# STEM.net
KiCad netlist of a schematic drawn in EAGLE
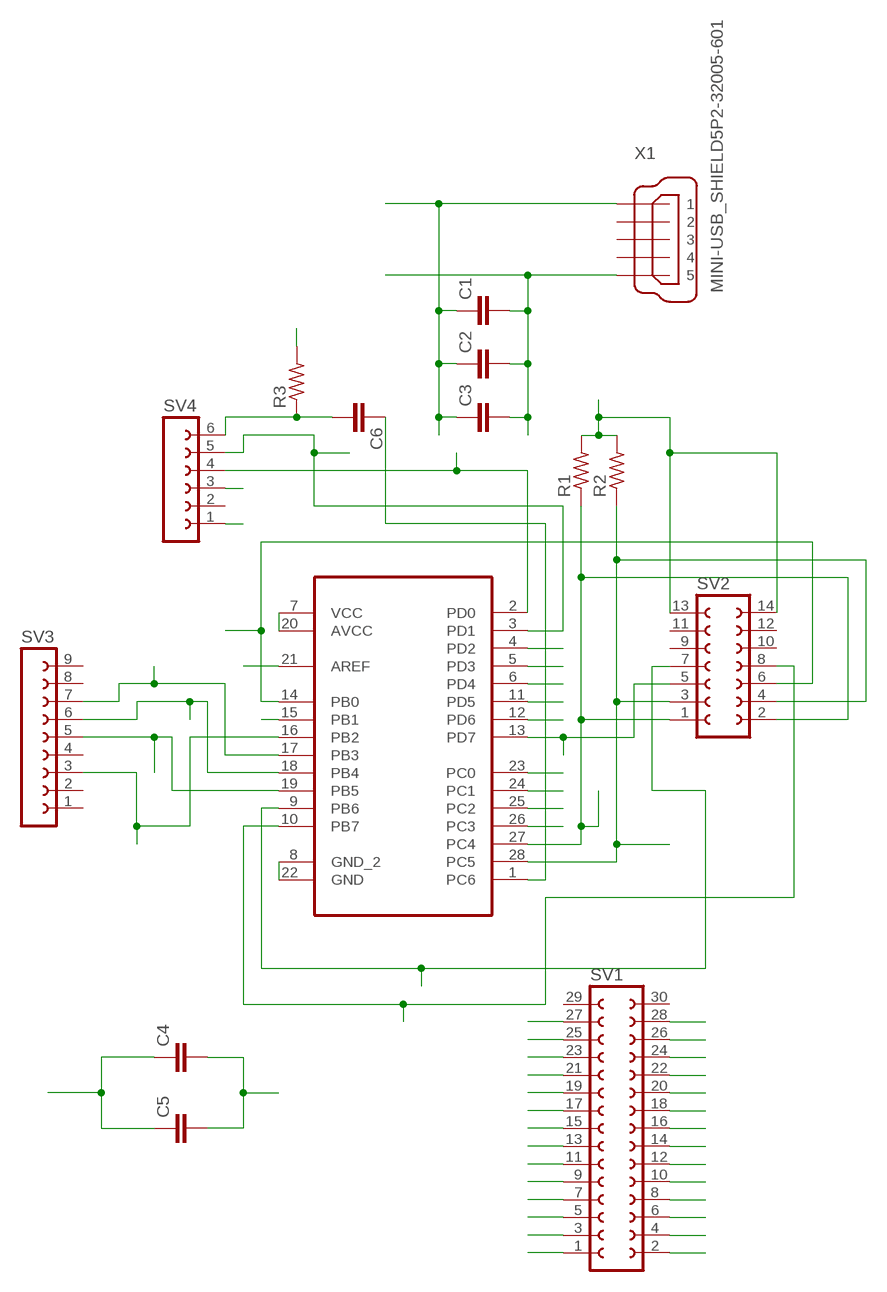
[diagram p0: schematic, sheet 1]

(export (version "E")
  (design (tool "Eeschema 10.0.6"))
  (components
    (comp (ref "C1")
      (value "C2,5-3")
      (footprint "eagle-import:C2.5-3")
      (libsource (lib "eagle-import") (part "C2,5-3"))
    )
    (comp (ref "C2")
      (value "C2,5-3")
      (footprint "eagle-import:C2.5-3")
      (libsource (lib "eagle-import") (part "C2,5-3"))
    )
    (comp (ref "C3")
      (value "C2,5-3")
      (footprint "eagle-import:C2.5-3")
      (libsource (lib "eagle-import") (part "C2,5-3"))
    )
    (comp (ref "C4")
      (value "C2,5-3")
      (footprint "eagle-import:C2.5-3")
      (libsource (lib "eagle-import") (part "C2,5-3"))
    )
    (comp (ref "C5")
      (value "C2,5-3")
      (footprint "eagle-import:C2.5-3")
      (libsource (lib "eagle-import") (part "C2,5-3"))
    )
    (comp (ref "C6")
      (value "C2,5-3")
      (footprint "eagle-import:C2.5-3")
      (libsource (lib "eagle-import") (part "C2,5-3"))
    )
    (comp (ref "R1")
      (value "R-US_0204/7")
      (footprint "eagle-import:0204_7")
      (libsource (lib "eagle-import") (part "R-US_0204/7"))
    )
    (comp (ref "R2")
      (value "R-US_0204/7")
      (footprint "eagle-import:0204_7")
      (libsource (lib "eagle-import") (part "R-US_0204/7"))
    )
    (comp (ref "R3")
      (value "R-US_0204/7")
      (footprint "eagle-import:0204_7")
      (libsource (lib "eagle-import") (part "R-US_0204/7"))
    )
    (comp (ref "SV1")
      (value "FE15-2")
      (footprint "eagle-import:FE15-2")
      (libsource (lib "eagle-import") (part "FE15-2"))
    )
    (comp (ref "SV2")
      (value "FE07-2")
      (footprint "eagle-import:FE07-2")
      (libsource (lib "eagle-import") (part "FE07-2"))
    )
    (comp (ref "SV3")
      (value "FE09-1")
      (footprint "eagle-import:FE09")
      (libsource (lib "eagle-import") (part "FE09-1"))
    )
    (comp (ref "SV4")
      (value "FE06-1")
      (footprint "eagle-import:FE06")
      (libsource (lib "eagle-import") (part "FE06-1"))
    )
    (comp (ref "U1")
      (value "ATMEGA328P-PU")
      (footprint "eagle-import:DIP254P762X457-28")
      (libsource (lib "eagle-import") (part "ATMEGA328P-PU"))
    )
    (comp (ref "X1")
      (value "MINI-USB_SHIELD5P2-32005-601")
      (footprint "eagle-import:32005-601")
      (libsource (lib "eagle-import") (part "MINI-USB_SHIELD5P2-32005-601"))
    )
  )
  (nets
    (net (code "1") (name "/AREF") (class "Default")
      (node (ref "C4") (pin "1") (pinfunction "1_1") (pintype "passive"))
      (node (ref "C5") (pin "1") (pinfunction "1_1") (pintype "passive"))
      (node (ref "SV1") (pin "14") (pinfunction "14_14") (pintype "passive"))
      (node (ref "U1") (pin "21") (pinfunction "AREF_21") (pintype "input"))
    )
    (net (code "2") (name "/GND") (class "Default")
      (node (ref "C1") (pin "2") (pinfunction "2_2") (pintype "passive"))
      (node (ref "C2") (pin "2") (pinfunction "2_2") (pintype "passive"))
      (node (ref "C3") (pin "2") (pinfunction "2_2") (pintype "passive"))
      (node (ref "C4") (pin "2") (pinfunction "2_2") (pintype "passive"))
      (node (ref "C5") (pin "2") (pinfunction "2_2") (pintype "passive"))
      (node (ref "SV1") (pin "13") (pinfunction "13_13") (pintype "passive"))
      (node (ref "SV1") (pin "16") (pinfunction "16_16") (pintype "passive"))
      (node (ref "SV4") (pin "1") (pinfunction "1_1") (pintype "passive"))
      (node (ref "U1") (pin "22") (pinfunction "GND_22") (pintype "passive"))
      (node (ref "U1") (pin "8") (pinfunction "GND_2_8") (pintype "passive"))
      (node (ref "X1") (pin "5") (pinfunction "5_5") (pintype "passive"))
    )
    (net (code "3") (name "/PB0") (class "Default")
      (node (ref "SV1") (pin "1") (pinfunction "1_1") (pintype "passive"))
      (node (ref "SV2") (pin "6") (pinfunction "6_6") (pintype "passive"))
      (node (ref "U1") (pin "14") (pinfunction "PB0_14") (pintype "bidirectional"))
    )
    (net (code "4") (name "/PB1") (class "Default")
      (node (ref "SV1") (pin "2") (pinfunction "2_2") (pintype "passive"))
      (node (ref "U1") (pin "15") (pinfunction "PB1_15") (pintype "bidirectional"))
    )
    (net (code "5") (name "/PB2") (class "Default")
      (node (ref "SV1") (pin "4") (pinfunction "4_4") (pintype "passive"))
      (node (ref "SV3") (pin "3") (pinfunction "3_3") (pintype "passive"))
      (node (ref "U1") (pin "16") (pinfunction "PB2_16") (pintype "bidirectional"))
    )
    (net (code "6") (name "/PB3") (class "Default")
      (node (ref "SV1") (pin "6") (pinfunction "6_6") (pintype "passive"))
      (node (ref "SV3") (pin "7") (pinfunction "7_7") (pintype "passive"))
      (node (ref "U1") (pin "17") (pinfunction "PB3_17") (pintype "bidirectional"))
    )
    (net (code "7") (name "/PB4") (class "Default")
      (node (ref "SV1") (pin "8") (pinfunction "8_8") (pintype "passive"))
      (node (ref "SV3") (pin "6") (pinfunction "6_6") (pintype "passive"))
      (node (ref "U1") (pin "18") (pinfunction "PB4_18") (pintype "bidirectional"))
    )
    (net (code "8") (name "/PB5") (class "Default")
      (node (ref "SV1") (pin "10") (pinfunction "10_10") (pintype "passive"))
      (node (ref "SV3") (pin "5") (pinfunction "5_5") (pintype "passive"))
      (node (ref "U1") (pin "19") (pinfunction "PB5_19") (pintype "bidirectional"))
    )
    (net (code "9") (name "/PB6") (class "Default")
      (node (ref "SV1") (pin "11") (pinfunction "11_11") (pintype "passive"))
      (node (ref "SV2") (pin "7") (pinfunction "7_7") (pintype "passive"))
      (node (ref "U1") (pin "9") (pinfunction "PB6_9") (pintype "bidirectional"))
    )
    (net (code "10") (name "/PB7") (class "Default")
      (node (ref "SV1") (pin "9") (pinfunction "9_9") (pintype "passive"))
      (node (ref "SV2") (pin "8") (pinfunction "8_8") (pintype "passive"))
      (node (ref "U1") (pin "10") (pinfunction "PB7_10") (pintype "bidirectional"))
    )
    (net (code "11") (name "/PC0") (class "Default")
      (node (ref "SV1") (pin "18") (pinfunction "18_18") (pintype "passive"))
      (node (ref "U1") (pin "23") (pinfunction "PC0_23") (pintype "bidirectional"))
    )
    (net (code "12") (name "/PC1") (class "Default")
      (node (ref "SV1") (pin "20") (pinfunction "20_20") (pintype "passive"))
      (node (ref "U1") (pin "24") (pinfunction "PC1_24") (pintype "bidirectional"))
    )
    (net (code "13") (name "/PC2") (class "Default")
      (node (ref "SV1") (pin "22") (pinfunction "22_22") (pintype "passive"))
      (node (ref "U1") (pin "25") (pinfunction "PC2_25") (pintype "bidirectional"))
    )
    (net (code "14") (name "/PC3") (class "Default")
      (node (ref "SV1") (pin "24") (pinfunction "24_24") (pintype "passive"))
      (node (ref "U1") (pin "26") (pinfunction "PC3_26") (pintype "bidirectional"))
    )
    (net (code "15") (name "/PC4") (class "Default")
      (node (ref "R1") (pin "1") (pinfunction "1_1") (pintype "passive"))
      (node (ref "SV1") (pin "26") (pinfunction "26_26") (pintype "passive"))
      (node (ref "SV2") (pin "1") (pinfunction "1_1") (pintype "passive"))
      (node (ref "SV2") (pin "2") (pinfunction "2_2") (pintype "passive"))
      (node (ref "U1") (pin "27") (pinfunction "PC4_27") (pintype "bidirectional"))
    )
    (net (code "16") (name "/PC5") (class "Default")
      (node (ref "R2") (pin "1") (pinfunction "1_1") (pintype "passive"))
      (node (ref "SV1") (pin "28") (pinfunction "28_28") (pintype "passive"))
      (node (ref "SV2") (pin "3") (pinfunction "3_3") (pintype "passive"))
      (node (ref "SV2") (pin "4") (pinfunction "4_4") (pintype "passive"))
      (node (ref "U1") (pin "28") (pinfunction "PC5_28") (pintype "bidirectional"))
    )
    (net (code "17") (name "/PC6") (class "Default")
      (node (ref "C6") (pin "1") (pinfunction "1_1") (pintype "passive"))
      (node (ref "SV1") (pin "27") (pinfunction "27_27") (pintype "passive"))
      (node (ref "U1") (pin "1") (pinfunction "PC6_1") (pintype "bidirectional"))
    )
    (net (code "18") (name "/PD0") (class "Default")
      (node (ref "SV1") (pin "25") (pinfunction "25_25") (pintype "passive"))
      (node (ref "SV4") (pin "4") (pinfunction "4_4") (pintype "passive"))
      (node (ref "U1") (pin "2") (pinfunction "PD0_2") (pintype "bidirectional"))
    )
    (net (code "19") (name "/PD1") (class "Default")
      (node (ref "SV1") (pin "23") (pinfunction "23_23") (pintype "passive"))
      (node (ref "SV4") (pin "5") (pinfunction "5_5") (pintype "passive"))
      (node (ref "U1") (pin "3") (pinfunction "PD1_3") (pintype "bidirectional"))
    )
    (net (code "20") (name "/PD2") (class "Default")
      (node (ref "SV1") (pin "21") (pinfunction "21_21") (pintype "passive"))
      (node (ref "U1") (pin "4") (pinfunction "PD2_4") (pintype "bidirectional"))
    )
    (net (code "21") (name "/PD3") (class "Default")
      (node (ref "SV1") (pin "19") (pinfunction "19_19") (pintype "passive"))
      (node (ref "U1") (pin "5") (pinfunction "PD3_5") (pintype "bidirectional"))
    )
    (net (code "22") (name "/PD4") (class "Default")
      (node (ref "SV1") (pin "17") (pinfunction "17_17") (pintype "passive"))
      (node (ref "U1") (pin "6") (pinfunction "PD4_6") (pintype "bidirectional"))
    )
    (net (code "23") (name "/PD5") (class "Default")
      (node (ref "SV1") (pin "7") (pinfunction "7_7") (pintype "passive"))
      (node (ref "U1") (pin "11") (pinfunction "PD5_11") (pintype "bidirectional"))
    )
    (net (code "24") (name "/PD6") (class "Default")
      (node (ref "SV1") (pin "5") (pinfunction "5_5") (pintype "passive"))
      (node (ref "U1") (pin "12") (pinfunction "PD6_12") (pintype "bidirectional"))
    )
    (net (code "25") (name "/PD7") (class "Default")
      (node (ref "SV1") (pin "3") (pinfunction "3_3") (pintype "passive"))
      (node (ref "SV2") (pin "5") (pinfunction "5_5") (pintype "passive"))
      (node (ref "U1") (pin "13") (pinfunction "PD7_13") (pintype "bidirectional"))
    )
    (net (code "26") (name "/VCC") (class "Default")
      (node (ref "C1") (pin "1") (pinfunction "1_1") (pintype "passive"))
      (node (ref "C2") (pin "1") (pinfunction "1_1") (pintype "passive"))
      (node (ref "C3") (pin "1") (pinfunction "1_1") (pintype "passive"))
      (node (ref "R1") (pin "2") (pinfunction "2_2") (pintype "passive"))
      (node (ref "R2") (pin "2") (pinfunction "2_2") (pintype "passive"))
      (node (ref "R3") (pin "2") (pinfunction "2_2") (pintype "passive"))
      (node (ref "SV1") (pin "12") (pinfunction "12_12") (pintype "passive"))
      (node (ref "SV1") (pin "15") (pinfunction "15_15") (pintype "passive"))
      (node (ref "SV2") (pin "13") (pinfunction "13_13") (pintype "passive"))
      (node (ref "SV2") (pin "14") (pinfunction "14_14") (pintype "passive"))
      (node (ref "SV4") (pin "3") (pinfunction "3_3") (pintype "passive"))
      (node (ref "U1") (pin "20") (pinfunction "AVCC_20") (pintype "power_in"))
      (node (ref "U1") (pin "7") (pinfunction "VCC_7") (pintype "power_in"))
      (node (ref "X1") (pin "1") (pinfunction "1_1") (pintype "passive"))
    )
    (net (code "27") (name "Net-(C6-Pad2)") (class "Default")
      (node (ref "C6") (pin "2") (pinfunction "2_2") (pintype "passive"))
      (node (ref "R3") (pin "1") (pinfunction "1_1") (pintype "passive"))
      (node (ref "SV4") (pin "6") (pinfunction "6_6") (pintype "passive"))
    )
    (net (code "28") (name "unconnected-(SV1-Pad29)") (class "Default")
      (node (ref "SV1") (pin "29") (pinfunction "29_29") (pintype "passive"))
    )
    (net (code "29") (name "unconnected-(SV1-Pad30)") (class "Default")
      (node (ref "SV1") (pin "30") (pinfunction "30_30") (pintype "passive"))
    )
    (net (code "30") (name "unconnected-(SV2-Pad9)") (class "Default")
      (node (ref "SV2") (pin "9") (pinfunction "9_9") (pintype "passive"))
    )
    (net (code "31") (name "unconnected-(SV2-Pad10)") (class "Default")
      (node (ref "SV2") (pin "10") (pinfunction "10_10") (pintype "passive"))
    )
    (net (code "32") (name "unconnected-(SV2-Pad11)") (class "Default")
      (node (ref "SV2") (pin "11") (pinfunction "11_11") (pintype "passive"))
    )
    (net (code "33") (name "unconnected-(SV2-Pad12)") (class "Default")
      (node (ref "SV2") (pin "12") (pinfunction "12_12") (pintype "passive"))
    )
    (net (code "34") (name "unconnected-(SV3-Pad1)") (class "Default")
      (node (ref "SV3") (pin "1") (pinfunction "1_1") (pintype "passive"))
    )
    (net (code "35") (name "unconnected-(SV3-Pad2)") (class "Default")
      (node (ref "SV3") (pin "2") (pinfunction "2_2") (pintype "passive"))
    )
    (net (code "36") (name "unconnected-(SV3-Pad4)") (class "Default")
      (node (ref "SV3") (pin "4") (pinfunction "4_4") (pintype "passive"))
    )
    (net (code "37") (name "unconnected-(SV3-Pad8)") (class "Default")
      (node (ref "SV3") (pin "8") (pinfunction "8_8") (pintype "passive"))
    )
    (net (code "38") (name "unconnected-(SV3-Pad9)") (class "Default")
      (node (ref "SV3") (pin "9") (pinfunction "9_9") (pintype "passive"))
    )
    (net (code "39") (name "unconnected-(SV4-Pad2)") (class "Default")
      (node (ref "SV4") (pin "2") (pinfunction "2_2") (pintype "passive"))
    )
    (net (code "40") (name "unconnected-(X1-Pad2)") (class "Default")
      (node (ref "X1") (pin "2") (pinfunction "2_2") (pintype "passive"))
    )
    (net (code "41") (name "unconnected-(X1-Pad3)") (class "Default")
      (node (ref "X1") (pin "3") (pinfunction "3_3") (pintype "passive"))
    )
    (net (code "42") (name "unconnected-(X1-Pad4)") (class "Default")
      (node (ref "X1") (pin "4") (pinfunction "4_4") (pintype "passive"))
    )
  )
)
